# VNC1L.net
KiCad netlist of a schematic drawn in EAGLE
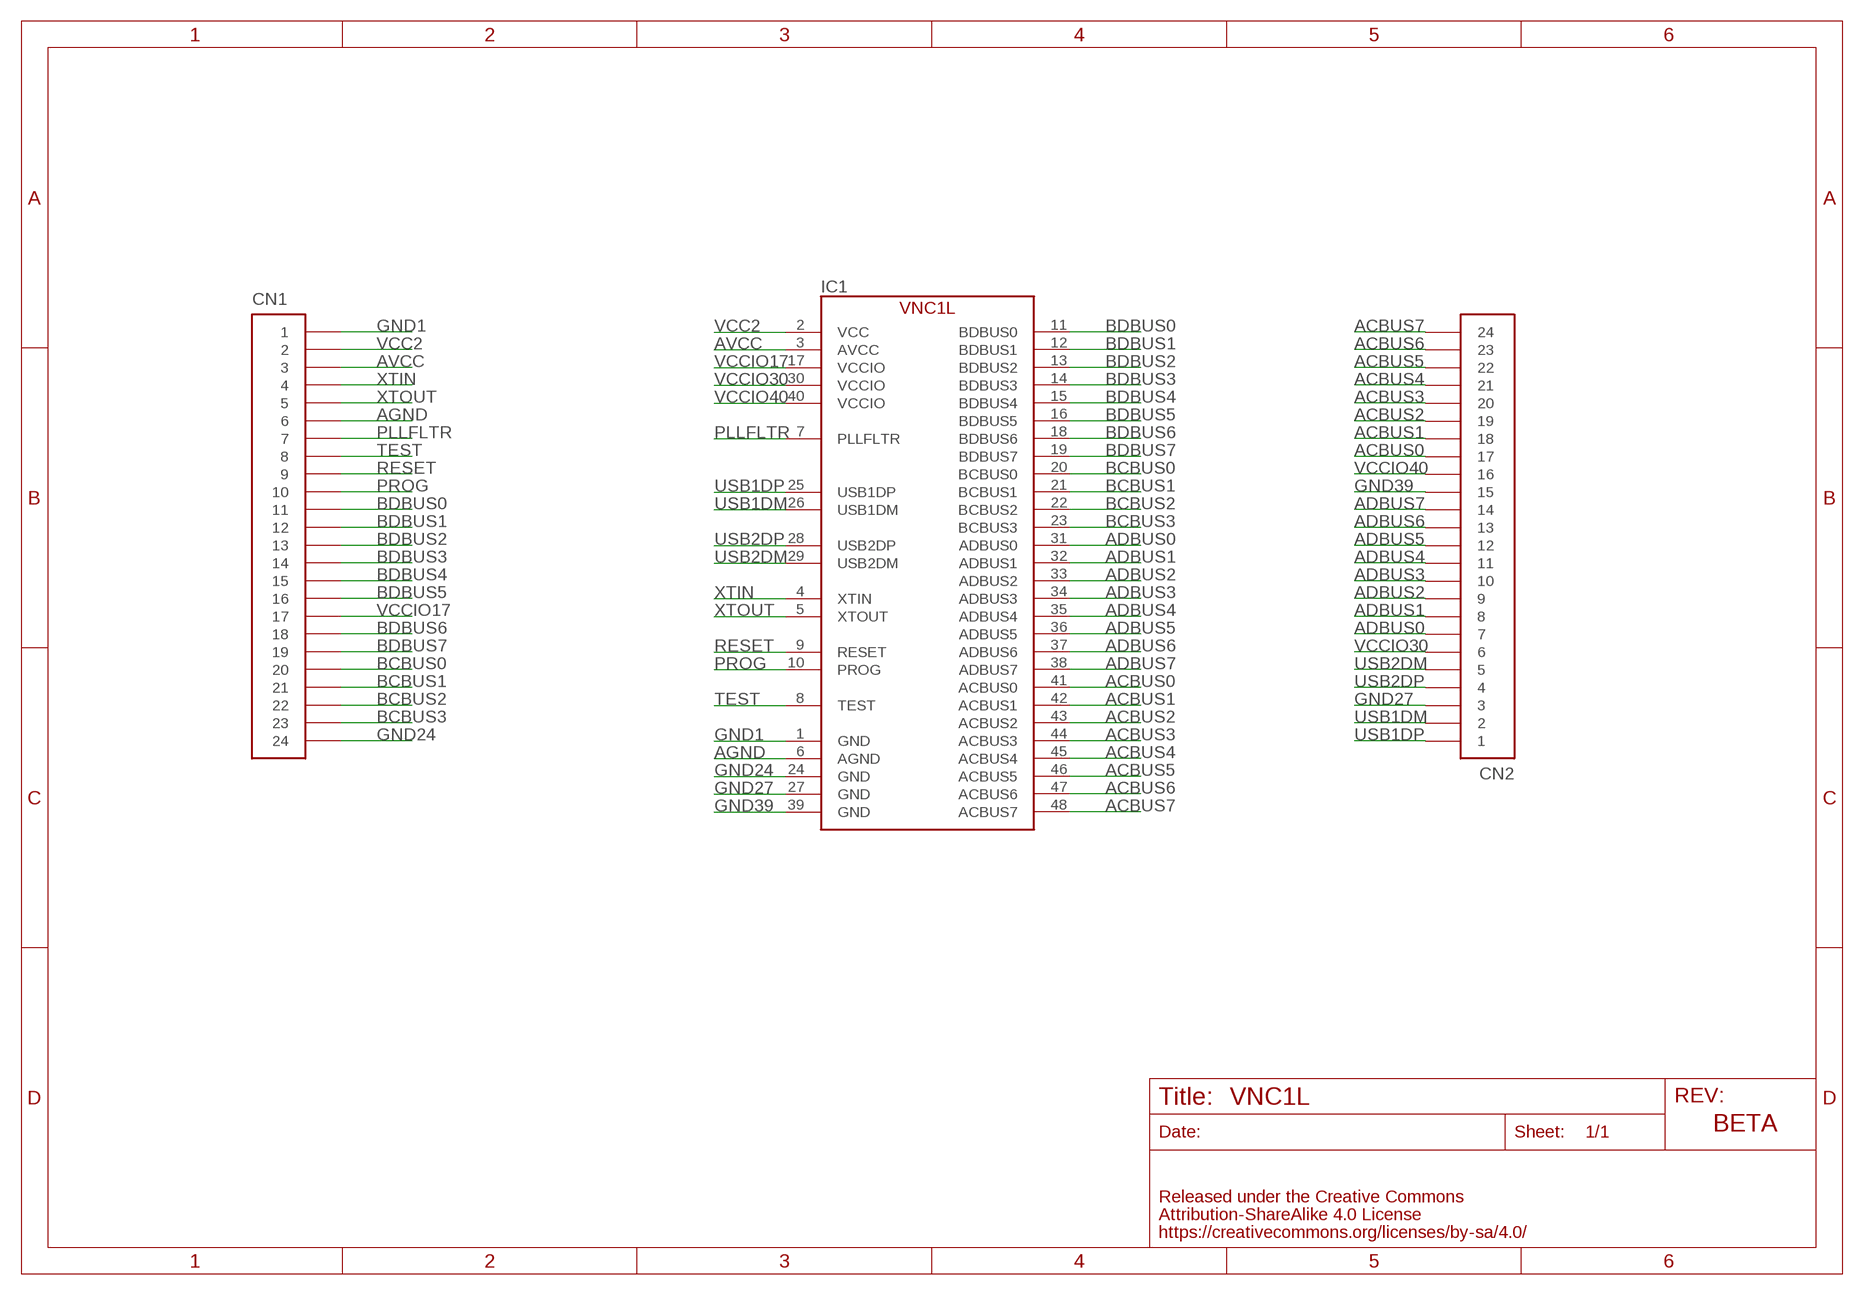
[diagram p0: schematic, sheet 1]

(export (version "E")
  (design (tool "Eeschema 10.0.6"))
  (components
    (comp (ref "CN1")
      (value "PIN_HEADER_1X24")
      (footprint "eagle-import:PIN_1X24_SNEAKY")
      (libsource (lib "eagle-import") (part "PIN_HEADER_1X24"))
    )
    (comp (ref "CN2")
      (value "PIN_HEADER_1X24")
      (footprint "eagle-import:PIN_1X24_SNEAKY")
      (libsource (lib "eagle-import") (part "PIN_HEADER_1X24"))
    )
    (comp (ref "IC1")
      (value "VNC1L-1A")
      (footprint "eagle-import:LQFP-48")
      (libsource (lib "eagle-import") (part "VNC1L-1A"))
    )
  )
  (nets
    (net (code "1") (name "/ACBUS0") (class "Default")
      (node (ref "CN2") (pin "17") (pinfunction "17_17") (pintype "bidirectional"))
      (node (ref "IC1") (pin "41") (pinfunction "ACBUS0_41") (pintype "bidirectional"))
    )
    (net (code "2") (name "/ACBUS1") (class "Default")
      (node (ref "CN2") (pin "18") (pinfunction "18_18") (pintype "bidirectional"))
      (node (ref "IC1") (pin "42") (pinfunction "ACBUS1_42") (pintype "bidirectional"))
    )
    (net (code "3") (name "/ACBUS2") (class "Default")
      (node (ref "CN2") (pin "19") (pinfunction "19_19") (pintype "bidirectional"))
      (node (ref "IC1") (pin "43") (pinfunction "ACBUS2_43") (pintype "bidirectional"))
    )
    (net (code "4") (name "/ACBUS3") (class "Default")
      (node (ref "CN2") (pin "20") (pinfunction "20_20") (pintype "bidirectional"))
      (node (ref "IC1") (pin "44") (pinfunction "ACBUS3_44") (pintype "bidirectional"))
    )
    (net (code "5") (name "/ACBUS4") (class "Default")
      (node (ref "CN2") (pin "21") (pinfunction "21_21") (pintype "bidirectional"))
      (node (ref "IC1") (pin "45") (pinfunction "ACBUS4_45") (pintype "bidirectional"))
    )
    (net (code "6") (name "/ACBUS5") (class "Default")
      (node (ref "CN2") (pin "22") (pinfunction "22_22") (pintype "bidirectional"))
      (node (ref "IC1") (pin "46") (pinfunction "ACBUS5_46") (pintype "bidirectional"))
    )
    (net (code "7") (name "/ACBUS6") (class "Default")
      (node (ref "CN2") (pin "23") (pinfunction "23_23") (pintype "bidirectional"))
      (node (ref "IC1") (pin "47") (pinfunction "ACBUS6_47") (pintype "bidirectional"))
    )
    (net (code "8") (name "/ACBUS7") (class "Default")
      (node (ref "CN2") (pin "24") (pinfunction "24_24") (pintype "bidirectional"))
      (node (ref "IC1") (pin "48") (pinfunction "ACBUS7_48") (pintype "bidirectional"))
    )
    (net (code "9") (name "/ADBUS0") (class "Default")
      (node (ref "CN2") (pin "7") (pinfunction "7_7") (pintype "bidirectional"))
      (node (ref "IC1") (pin "31") (pinfunction "ADBUS0_31") (pintype "bidirectional"))
    )
    (net (code "10") (name "/ADBUS1") (class "Default")
      (node (ref "CN2") (pin "8") (pinfunction "8_8") (pintype "bidirectional"))
      (node (ref "IC1") (pin "32") (pinfunction "ADBUS1_32") (pintype "bidirectional"))
    )
    (net (code "11") (name "/ADBUS2") (class "Default")
      (node (ref "CN2") (pin "9") (pinfunction "9_9") (pintype "bidirectional"))
      (node (ref "IC1") (pin "33") (pinfunction "ADBUS2_33") (pintype "bidirectional"))
    )
    (net (code "12") (name "/ADBUS3") (class "Default")
      (node (ref "CN2") (pin "10") (pinfunction "10_10") (pintype "bidirectional"))
      (node (ref "IC1") (pin "34") (pinfunction "ADBUS3_34") (pintype "bidirectional"))
    )
    (net (code "13") (name "/ADBUS4") (class "Default")
      (node (ref "CN2") (pin "11") (pinfunction "11_11") (pintype "bidirectional"))
      (node (ref "IC1") (pin "35") (pinfunction "ADBUS4_35") (pintype "bidirectional"))
    )
    (net (code "14") (name "/ADBUS5") (class "Default")
      (node (ref "CN2") (pin "12") (pinfunction "12_12") (pintype "bidirectional"))
      (node (ref "IC1") (pin "36") (pinfunction "ADBUS5_36") (pintype "bidirectional"))
    )
    (net (code "15") (name "/ADBUS6") (class "Default")
      (node (ref "CN2") (pin "13") (pinfunction "13_13") (pintype "bidirectional"))
      (node (ref "IC1") (pin "37") (pinfunction "ADBUS6_37") (pintype "bidirectional"))
    )
    (net (code "16") (name "/ADBUS7") (class "Default")
      (node (ref "CN2") (pin "14") (pinfunction "14_14") (pintype "bidirectional"))
      (node (ref "IC1") (pin "38") (pinfunction "ADBUS7_38") (pintype "bidirectional"))
    )
    (net (code "17") (name "/AGND") (class "Default")
      (node (ref "CN1") (pin "6") (pinfunction "6_6") (pintype "bidirectional"))
      (node (ref "IC1") (pin "6") (pinfunction "AGND_6") (pintype "bidirectional"))
    )
    (net (code "18") (name "/AVCC") (class "Default")
      (node (ref "CN1") (pin "3") (pinfunction "3_3") (pintype "bidirectional"))
      (node (ref "IC1") (pin "3") (pinfunction "AVCC_3") (pintype "bidirectional"))
    )
    (net (code "19") (name "/BCBUS0") (class "Default")
      (node (ref "CN1") (pin "20") (pinfunction "20_20") (pintype "bidirectional"))
      (node (ref "IC1") (pin "20") (pinfunction "BCBUS0_20") (pintype "bidirectional"))
    )
    (net (code "20") (name "/BCBUS1") (class "Default")
      (node (ref "CN1") (pin "21") (pinfunction "21_21") (pintype "bidirectional"))
      (node (ref "IC1") (pin "21") (pinfunction "BCBUS1_21") (pintype "bidirectional"))
    )
    (net (code "21") (name "/BCBUS2") (class "Default")
      (node (ref "CN1") (pin "22") (pinfunction "22_22") (pintype "bidirectional"))
      (node (ref "IC1") (pin "22") (pinfunction "BCBUS2_22") (pintype "bidirectional"))
    )
    (net (code "22") (name "/BCBUS3") (class "Default")
      (node (ref "CN1") (pin "23") (pinfunction "23_23") (pintype "bidirectional"))
      (node (ref "IC1") (pin "23") (pinfunction "BCBUS3_23") (pintype "bidirectional"))
    )
    (net (code "23") (name "/BDBUS0") (class "Default")
      (node (ref "CN1") (pin "11") (pinfunction "11_11") (pintype "bidirectional"))
      (node (ref "IC1") (pin "11") (pinfunction "BDBUS0_11") (pintype "bidirectional"))
    )
    (net (code "24") (name "/BDBUS1") (class "Default")
      (node (ref "CN1") (pin "12") (pinfunction "12_12") (pintype "bidirectional"))
      (node (ref "IC1") (pin "12") (pinfunction "BDBUS1_12") (pintype "bidirectional"))
    )
    (net (code "25") (name "/BDBUS2") (class "Default")
      (node (ref "CN1") (pin "13") (pinfunction "13_13") (pintype "bidirectional"))
      (node (ref "IC1") (pin "13") (pinfunction "BDBUS2_13") (pintype "bidirectional"))
    )
    (net (code "26") (name "/BDBUS3") (class "Default")
      (node (ref "CN1") (pin "14") (pinfunction "14_14") (pintype "bidirectional"))
      (node (ref "IC1") (pin "14") (pinfunction "BDBUS3_14") (pintype "bidirectional"))
    )
    (net (code "27") (name "/BDBUS4") (class "Default")
      (node (ref "CN1") (pin "15") (pinfunction "15_15") (pintype "bidirectional"))
      (node (ref "IC1") (pin "15") (pinfunction "BDBUS4_15") (pintype "bidirectional"))
    )
    (net (code "28") (name "/BDBUS5") (class "Default")
      (node (ref "CN1") (pin "16") (pinfunction "16_16") (pintype "bidirectional"))
      (node (ref "IC1") (pin "16") (pinfunction "BDBUS5_16") (pintype "bidirectional"))
    )
    (net (code "29") (name "/BDBUS6") (class "Default")
      (node (ref "CN1") (pin "18") (pinfunction "18_18") (pintype "bidirectional"))
      (node (ref "IC1") (pin "18") (pinfunction "BDBUS6_18") (pintype "bidirectional"))
    )
    (net (code "30") (name "/BDBUS7") (class "Default")
      (node (ref "CN1") (pin "19") (pinfunction "19_19") (pintype "bidirectional"))
      (node (ref "IC1") (pin "19") (pinfunction "BDBUS7_19") (pintype "bidirectional"))
    )
    (net (code "31") (name "/GND1") (class "Default")
      (node (ref "CN1") (pin "1") (pinfunction "1_1") (pintype "bidirectional"))
      (node (ref "IC1") (pin "1") (pinfunction "GND_1") (pintype "bidirectional"))
    )
    (net (code "32") (name "/GND24") (class "Default")
      (node (ref "CN1") (pin "24") (pinfunction "24_24") (pintype "bidirectional"))
      (node (ref "IC1") (pin "24") (pinfunction "GND_24") (pintype "bidirectional"))
    )
    (net (code "33") (name "/GND27") (class "Default")
      (node (ref "CN2") (pin "3") (pinfunction "3_3") (pintype "bidirectional"))
      (node (ref "IC1") (pin "27") (pinfunction "GND_27") (pintype "bidirectional"))
    )
    (net (code "34") (name "/GND39") (class "Default")
      (node (ref "CN2") (pin "15") (pinfunction "15_15") (pintype "bidirectional"))
      (node (ref "IC1") (pin "39") (pinfunction "GND_39") (pintype "bidirectional"))
    )
    (net (code "35") (name "/PLLFLTR") (class "Default")
      (node (ref "CN1") (pin "7") (pinfunction "7_7") (pintype "bidirectional"))
      (node (ref "IC1") (pin "7") (pinfunction "PLLFLTR_7") (pintype "bidirectional"))
    )
    (net (code "36") (name "/PROG") (class "Default")
      (node (ref "CN1") (pin "10") (pinfunction "10_10") (pintype "bidirectional"))
      (node (ref "IC1") (pin "10") (pinfunction "PROG_10") (pintype "bidirectional"))
    )
    (net (code "37") (name "/RESET") (class "Default")
      (node (ref "CN1") (pin "9") (pinfunction "9_9") (pintype "bidirectional"))
      (node (ref "IC1") (pin "9") (pinfunction "RESET_9") (pintype "bidirectional"))
    )
    (net (code "38") (name "/TEST") (class "Default")
      (node (ref "CN1") (pin "8") (pinfunction "8_8") (pintype "bidirectional"))
      (node (ref "IC1") (pin "8") (pinfunction "TEST_8") (pintype "bidirectional"))
    )
    (net (code "39") (name "/USB1DM") (class "Default")
      (node (ref "CN2") (pin "2") (pinfunction "2_2") (pintype "bidirectional"))
      (node (ref "IC1") (pin "26") (pinfunction "USB1DM_26") (pintype "bidirectional"))
    )
    (net (code "40") (name "/USB1DP") (class "Default")
      (node (ref "CN2") (pin "1") (pinfunction "1_1") (pintype "bidirectional"))
      (node (ref "IC1") (pin "25") (pinfunction "USB1DP_25") (pintype "bidirectional"))
    )
    (net (code "41") (name "/USB2DM") (class "Default")
      (node (ref "CN2") (pin "5") (pinfunction "5_5") (pintype "bidirectional"))
      (node (ref "IC1") (pin "29") (pinfunction "USB2DM_29") (pintype "bidirectional"))
    )
    (net (code "42") (name "/USB2DP") (class "Default")
      (node (ref "CN2") (pin "4") (pinfunction "4_4") (pintype "bidirectional"))
      (node (ref "IC1") (pin "28") (pinfunction "USB2DP_28") (pintype "bidirectional"))
    )
    (net (code "43") (name "/VCC2") (class "Default")
      (node (ref "CN1") (pin "2") (pinfunction "2_2") (pintype "bidirectional"))
      (node (ref "IC1") (pin "2") (pinfunction "VCC_2") (pintype "bidirectional"))
    )
    (net (code "44") (name "/VCCIO17") (class "Default")
      (node (ref "CN1") (pin "17") (pinfunction "17_17") (pintype "bidirectional"))
      (node (ref "IC1") (pin "17") (pinfunction "VCCIO_17") (pintype "bidirectional"))
    )
    (net (code "45") (name "/VCCIO30") (class "Default")
      (node (ref "CN2") (pin "6") (pinfunction "6_6") (pintype "bidirectional"))
      (node (ref "IC1") (pin "30") (pinfunction "VCCIO_30") (pintype "bidirectional"))
    )
    (net (code "46") (name "/VCCIO40") (class "Default")
      (node (ref "CN2") (pin "16") (pinfunction "16_16") (pintype "bidirectional"))
      (node (ref "IC1") (pin "40") (pinfunction "VCCIO_40") (pintype "bidirectional"))
    )
    (net (code "47") (name "/XTIN") (class "Default")
      (node (ref "CN1") (pin "4") (pinfunction "4_4") (pintype "bidirectional"))
      (node (ref "IC1") (pin "4") (pinfunction "XTIN_4") (pintype "bidirectional"))
    )
    (net (code "48") (name "/XTOUT") (class "Default")
      (node (ref "CN1") (pin "5") (pinfunction "5_5") (pintype "bidirectional"))
      (node (ref "IC1") (pin "5") (pinfunction "XTOUT_5") (pintype "bidirectional"))
    )
  )
)
